# USBFX2LP_1.net
KiCad netlist of a schematic drawn in Altium Designer
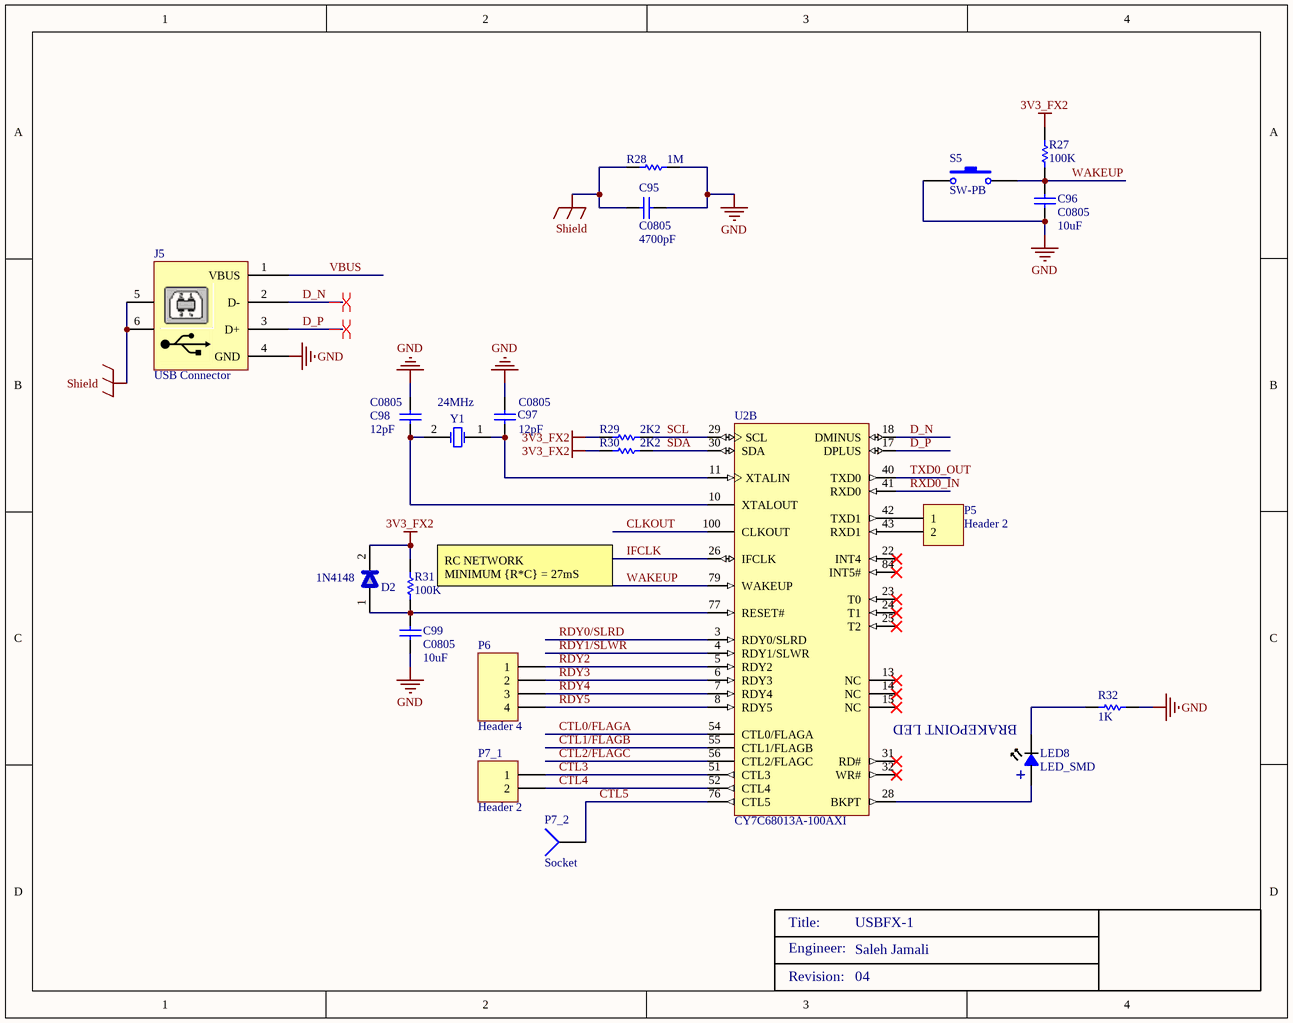
[diagram p0: USBFX2LP_1.SchDoc]

(export (version "E")
  (design (tool "Eeschema 10.0.6"))
  (components
    (comp (ref "C95")
      (value "C0805")
      (footprint "0805")
      (description "Ceramic Chip Capacitor - Standard")
      (fields (field (name "ALTIUM_VALUE") "4700pF") (field (name "PUBLISHER") "Altium Limited"))
      (libsource (lib "KEMET Chip Capacitor") (part "C0805"))
    )
    (comp (ref "C96")
      (value "C0805")
      (footprint "0805")
      (description "Ceramic Chip Capacitor - Standard")
      (fields (field (name "ALTIUM_VALUE") "10uF") (field (name "PUBLISHER") "Altium Limited"))
      (libsource (lib "KEMET Chip Capacitor") (part "C0805"))
    )
    (comp (ref "C97")
      (value "C0805")
      (footprint "0805")
      (description "Ceramic Chip Capacitor - Standard")
      (fields (field (name "ALTIUM_VALUE") "12pF") (field (name "PUBLISHER") "Altium Limited"))
      (libsource (lib "KEMET Chip Capacitor") (part "C0805"))
    )
    (comp (ref "C98")
      (value "C0805")
      (footprint "0805")
      (description "Ceramic Chip Capacitor - Standard")
      (fields (field (name "ALTIUM_VALUE") "12pF") (field (name "PUBLISHER") "Altium Limited"))
      (libsource (lib "KEMET Chip Capacitor") (part "C0805"))
    )
    (comp (ref "C99")
      (value "C0805")
      (footprint "0805")
      (description "Ceramic Chip Capacitor - Standard")
      (fields (field (name "ALTIUM_VALUE") "10uF") (field (name "PUBLISHER") "Altium Limited"))
      (libsource (lib "KEMET Chip Capacitor") (part "C0805"))
    )
    (comp (ref "D2")
      (value "1N4148")
      (footprint "MELF35")
      (description "melf 35 general purpose diode")
      (libsource (lib "Diode_MELF35") (part "Diode_SMD"))
    )
    (comp (ref "J5")
      (value "USB Connector")
      (footprint "USB2.5-2H4E")
      (description "USB Connector-B Type")
      (fields (field (name "DESIGNER") "Eng. Saeid Jorablo"))
      (libsource (lib "MegaLIB") (part "USB"))
    )
    (comp (ref "LED8") (value "LED_SMD") (footprint "LED_805") (libsource (lib "LED_PRJCT") (part "LED_SMD")))
    (comp (ref "P5")
      (value "Header 2")
      (footprint "HDR1X2")
      (description "Header, 2-Pin")
      (fields (field (name "PUBLISHER") "Altium Limited"))
      (libsource (lib "") (part "Header 2_1"))
    )
    (comp (ref "P6")
      (value "Header 4")
      (footprint "HDR1X4")
      (description "Header, 4-Pin")
      (fields (field (name "PUBLISHER") "Altium Limited"))
      (libsource (lib "Miscellaneous Connectors") (part "Header 4"))
    )
    (comp (ref "P7_1")
      (value "Header 2")
      (footprint "HDR1X2")
      (description "Header, 2-Pin")
      (fields (field (name "PUBLISHER") "Altium Limited"))
      (libsource (lib "Miscellaneous Connectors") (part "Header 2"))
    )
    (comp (ref "P7_2")
      (value "Socket")
      (footprint "PIN1")
      (fields (field (name "PUBLISHER") "Altium Limited"))
      (libsource (lib "Miscellaneous Connectors") (part "Socket"))
    )
    (comp (ref "R27")
      (value "100K")
      (footprint "ERA-0805")
      (fields (field (name "PUBLISHER") "Altium Limited"))
      (libsource (lib "Panasonic Resistor") (part "ERA6Y"))
    )
    (comp (ref "R28")
      (value "1M")
      (footprint "ERA-0805")
      (fields (field (name "PUBLISHER") "Altium Limited"))
      (libsource (lib "Panasonic Resistor") (part "ERA6Y"))
    )
    (comp (ref "R29")
      (value "2K2")
      (footprint "ERA-0805")
      (fields (field (name "PUBLISHER") "Altium Limited"))
      (libsource (lib "Panasonic Resistor") (part "ERA6Y"))
    )
    (comp (ref "R30")
      (value "2K2")
      (footprint "ERA-0805")
      (fields (field (name "PUBLISHER") "Altium Limited"))
      (libsource (lib "Panasonic Resistor") (part "ERA6Y"))
    )
    (comp (ref "R31")
      (value "100K")
      (footprint "ERA-0805")
      (fields (field (name "PUBLISHER") "Altium Limited"))
      (libsource (lib "Panasonic Resistor") (part "ERA6Y"))
    )
    (comp (ref "R32")
      (value "1K")
      (footprint "ERA-0805")
      (fields (field (name "PUBLISHER") "Altium Limited"))
      (libsource (lib "Panasonic Resistor") (part "ERA6Y"))
    )
    (comp (ref "S5")
      (value "SW-PB")
      (footprint "SPST-2")
      (description "Switch")
      (fields (field (name "PUBLISHER") "Altium Limited"))
      (libsource (lib "Miscellaneous Devices") (part "SW-PB"))
    )
    (comp (ref "U2")
      (value "CY7C68013A-100AXI")
      (footprint "CYP-AX100RA_N")
      (fields (field (name "MANUFACTURER") "Cypress"))
      (libsource (lib "Cypress USB Controllers") (part "CY7C68013A-100AXI"))
    )
    (comp (ref "Y1")
      (value "24MHz")
      (footprint "HC-49U")
      (description "Crystal Oscillator")
      (fields (field (name "PUBLISHER") "Altium Limited"))
      (libsource (lib "ECS Crystal Oscillator") (part "ECS-10-13-1"))
    )
  )
  (nets
    (net (code "1") (name "/CLKOUT") (class "Default")
      (node (ref "U2") (pin "100") (pinfunction "CLKOUT_100") (pintype "tri_state"))
    )
    (net (code "2") (name "/CTL0{slash}FLAGA") (class "Default")
      (node (ref "U2") (pin "54") (pinfunction "CTL0/FLAGA_54") (pintype "tri_state"))
    )
    (net (code "3") (name "/CTL1{slash}FLAGB") (class "Default")
      (node (ref "U2") (pin "55") (pinfunction "CTL1/FLAGB_55") (pintype "tri_state"))
    )
    (net (code "4") (name "/CTL2{slash}FLAGC") (class "Default")
      (node (ref "U2") (pin "56") (pinfunction "CTL2/FLAGC_56") (pintype "tri_state"))
    )
    (net (code "5") (name "/CTL3") (class "Default")
      (node (ref "P7_1") (pin "1") (pinfunction "1_1") (pintype "passive"))
      (node (ref "U2") (pin "51") (pinfunction "CTL3_51") (pintype "output"))
    )
    (net (code "6") (name "/CTL4") (class "Default")
      (node (ref "P7_1") (pin "2") (pinfunction "2_2") (pintype "passive"))
      (node (ref "U2") (pin "52") (pinfunction "CTL4_52") (pintype "output"))
    )
    (net (code "7") (name "/CTL5") (class "Default")
      (node (ref "P7_2") (pin "1") (pinfunction "1_1") (pintype "passive"))
      (node (ref "U2") (pin "76") (pinfunction "CTL5_76") (pintype "output"))
    )
    (net (code "8") (name "/D_N") (class "Default")
      (node (ref "J5") (pin "2") (pinfunction "D-_2") (pintype "passive"))
      (node (ref "U2") (pin "18") (pinfunction "DMINUS_18") (pintype "bidirectional"))
    )
    (net (code "9") (name "/D_P") (class "Default")
      (node (ref "J5") (pin "3") (pinfunction "D+_3") (pintype "passive"))
      (node (ref "U2") (pin "17") (pinfunction "DPLUS_17") (pintype "bidirectional"))
    )
    (net (code "10") (name "/IFCLK") (class "Default")
      (node (ref "U2") (pin "26") (pinfunction "IFCLK_26") (pintype "bidirectional"))
    )
    (net (code "11") (name "/RDY0{slash}SLRD") (class "Default")
      (node (ref "U2") (pin "3") (pinfunction "RDY0/SLRD_3") (pintype "input"))
    )
    (net (code "12") (name "/RDY1{slash}SLWR") (class "Default")
      (node (ref "U2") (pin "4") (pinfunction "RDY1/SLWR_4") (pintype "input"))
    )
    (net (code "13") (name "/RDY2") (class "Default")
      (node (ref "P6") (pin "1") (pinfunction "1_1") (pintype "passive"))
      (node (ref "U2") (pin "5") (pinfunction "RDY2_5") (pintype "input"))
    )
    (net (code "14") (name "/RDY3") (class "Default")
      (node (ref "P6") (pin "2") (pinfunction "2_2") (pintype "passive"))
      (node (ref "U2") (pin "6") (pinfunction "RDY3_6") (pintype "input"))
    )
    (net (code "15") (name "/RDY4") (class "Default")
      (node (ref "P6") (pin "3") (pinfunction "3_3") (pintype "passive"))
      (node (ref "U2") (pin "7") (pinfunction "RDY4_7") (pintype "input"))
    )
    (net (code "16") (name "/RDY5") (class "Default")
      (node (ref "P6") (pin "4") (pinfunction "4_4") (pintype "passive"))
      (node (ref "U2") (pin "8") (pinfunction "RDY5_8") (pintype "input"))
    )
    (net (code "17") (name "/RXD0_IN") (class "Default")
      (node (ref "U2") (pin "41") (pinfunction "RXD0_41") (pintype "input"))
    )
    (net (code "18") (name "/SCL") (class "Default")
      (node (ref "R29") (pin "1") (pinfunction "1_1") (pintype "passive"))
      (node (ref "U2") (pin "29") (pinfunction "SCL_29") (pintype "bidirectional"))
    )
    (net (code "19") (name "/SDA") (class "Default")
      (node (ref "R30") (pin "1") (pinfunction "1_1") (pintype "passive"))
      (node (ref "U2") (pin "30") (pinfunction "SDA_30") (pintype "bidirectional"))
    )
    (net (code "20") (name "/TXD0_OUT") (class "Default")
      (node (ref "U2") (pin "40") (pinfunction "TXD0_40") (pintype "output"))
    )
    (net (code "21") (name "/VBUS") (class "Default")
      (node (ref "J5") (pin "1") (pinfunction "VBUS_1") (pintype "power_in"))
    )
    (net (code "22") (name "/WAKEUP") (class "Default")
      (node (ref "C96") (pin "2") (pinfunction "2_2") (pintype "passive"))
      (node (ref "R27") (pin "2") (pinfunction "2_2") (pintype "passive"))
      (node (ref "S5") (pin "2") (pinfunction "2_2") (pintype "passive"))
      (node (ref "U2") (pin "79") (pinfunction "WAKEUP_79") (pintype "input"))
    )
    (net (code "23") (name "3V3_FX2") (class "Default")
      (node (ref "D2") (pin "2") (pinfunction "2_2") (pintype "passive"))
      (node (ref "R27") (pin "1") (pinfunction "1_1") (pintype "passive"))
      (node (ref "R29") (pin "2") (pinfunction "2_2") (pintype "passive"))
      (node (ref "R30") (pin "2") (pinfunction "2_2") (pintype "passive"))
      (node (ref "R31") (pin "1") (pinfunction "1_1") (pintype "passive"))
    )
    (net (code "24") (name "GND") (class "Default")
      (node (ref "C95") (pin "2") (pinfunction "2_2") (pintype "passive"))
      (node (ref "C96") (pin "1") (pinfunction "1_1") (pintype "passive"))
      (node (ref "C97") (pin "1") (pinfunction "1_1") (pintype "passive"))
      (node (ref "C98") (pin "1") (pinfunction "1_1") (pintype "passive"))
      (node (ref "C99") (pin "1") (pinfunction "1_1") (pintype "passive"))
      (node (ref "J5") (pin "4") (pinfunction "GND_4") (pintype "power_in"))
      (node (ref "R28") (pin "1") (pinfunction "1_1") (pintype "passive"))
      (node (ref "R32") (pin "2") (pinfunction "2_2") (pintype "passive"))
      (node (ref "S5") (pin "1") (pinfunction "1_1") (pintype "passive"))
    )
    (net (code "25") (name "Net-(LED8-Pad2)") (class "Default")
      (node (ref "LED8") (pin "2") (pinfunction "2_2") (pintype "passive"))
      (node (ref "R32") (pin "1") (pinfunction "1_1") (pintype "passive"))
    )
    (net (code "26") (name "Net-(U2B-BKPT)") (class "Default")
      (node (ref "LED8") (pin "1") (pinfunction "1_1") (pintype "passive"))
      (node (ref "U2") (pin "28") (pinfunction "BKPT_28") (pintype "output"))
    )
    (net (code "27") (name "Net-(U2B-RESET#)") (class "Default")
      (node (ref "C99") (pin "2") (pinfunction "2_2") (pintype "passive"))
      (node (ref "D2") (pin "1") (pinfunction "1_1") (pintype "passive"))
      (node (ref "R31") (pin "2") (pinfunction "2_2") (pintype "passive"))
      (node (ref "U2") (pin "77") (pinfunction "RESET#_77") (pintype "input"))
    )
    (net (code "28") (name "Net-(U2B-RXD1)") (class "Default")
      (node (ref "P5") (pin "2") (pinfunction "2_2") (pintype "passive"))
      (node (ref "U2") (pin "43") (pinfunction "RXD1_43") (pintype "input"))
    )
    (net (code "29") (name "Net-(U2B-TXD1)") (class "Default")
      (node (ref "P5") (pin "1") (pinfunction "1_1") (pintype "passive"))
      (node (ref "U2") (pin "42") (pinfunction "TXD1_42") (pintype "output"))
    )
    (net (code "30") (name "Net-(U2B-XTALIN)") (class "Default")
      (node (ref "C97") (pin "2") (pinfunction "2_2") (pintype "passive"))
      (node (ref "U2") (pin "11") (pinfunction "XTALIN_11") (pintype "input"))
      (node (ref "Y1") (pin "1") (pinfunction "OSC1_1") (pintype "passive"))
    )
    (net (code "31") (name "Net-(U2B-XTALOUT)") (class "Default")
      (node (ref "C98") (pin "2") (pinfunction "2_2") (pintype "passive"))
      (node (ref "U2") (pin "10") (pinfunction "XTALOUT_10") (pintype "passive"))
      (node (ref "Y1") (pin "2") (pinfunction "OSC2_2") (pintype "passive"))
    )
    (net (code "32") (name "Shield") (class "Default")
      (node (ref "C95") (pin "1") (pinfunction "1_1") (pintype "passive"))
      (node (ref "J5") (pin "5") (pinfunction "5_5") (pintype "passive"))
      (node (ref "J5") (pin "6") (pinfunction "6_6") (pintype "passive"))
      (node (ref "R28") (pin "2") (pinfunction "2_2") (pintype "passive"))
    )
    (net (code "33") (name "unconnected-(U2B-INT4-Pad22)") (class "Default")
      (node (ref "U2") (pin "22") (pinfunction "INT4_22") (pintype "input+no_connect"))
    )
    (net (code "34") (name "unconnected-(U2B-INT5#-Pad84)") (class "Default")
      (node (ref "U2") (pin "84") (pinfunction "INT5#_84") (pintype "input+no_connect"))
    )
    (net (code "35") (name "unconnected-(U2B-NC-Pad13)") (class "Default")
      (node (ref "U2") (pin "13") (pinfunction "NC_13") (pintype "passive+no_connect"))
    )
    (net (code "36") (name "unconnected-(U2B-NC-Pad14)") (class "Default")
      (node (ref "U2") (pin "14") (pinfunction "NC_14") (pintype "passive+no_connect"))
    )
    (net (code "37") (name "unconnected-(U2B-NC-Pad15)") (class "Default")
      (node (ref "U2") (pin "15") (pinfunction "NC_15") (pintype "passive+no_connect"))
    )
    (net (code "38") (name "unconnected-(U2B-RD#-Pad31)") (class "Default")
      (node (ref "U2") (pin "31") (pinfunction "RD#_31") (pintype "output+no_connect"))
    )
    (net (code "39") (name "unconnected-(U2B-T0-Pad23)") (class "Default")
      (node (ref "U2") (pin "23") (pinfunction "T0_23") (pintype "input+no_connect"))
    )
    (net (code "40") (name "unconnected-(U2B-T1-Pad24)") (class "Default")
      (node (ref "U2") (pin "24") (pinfunction "T1_24") (pintype "input+no_connect"))
    )
    (net (code "41") (name "unconnected-(U2B-T2-Pad25)") (class "Default")
      (node (ref "U2") (pin "25") (pinfunction "T2_25") (pintype "input+no_connect"))
    )
    (net (code "42") (name "unconnected-(U2B-WR#-Pad32)") (class "Default")
      (node (ref "U2") (pin "32") (pinfunction "WR#_32") (pintype "output+no_connect"))
    )
  )
)
